# FonteTensaoVariavel.net
KiCad netlist of a schematic drawn in EAGLE
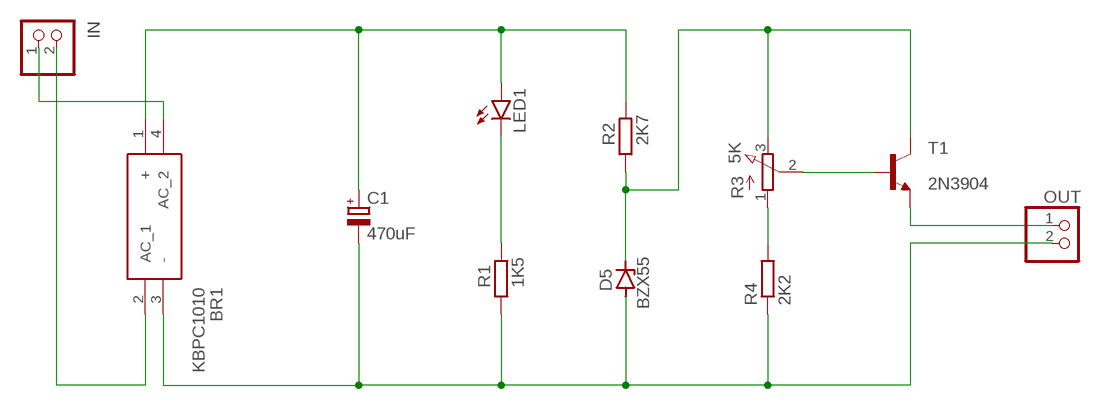
[diagram p0: schematic, sheet 1]

(export (version "E")
  (design (tool "Eeschema 10.0.6"))
  (components
    (comp (ref "BR1")
      (value "KBPC1010")
      (footprint "eagle-import:KBPC1010")
      (libsource (lib "eagle-import") (part "KBPC1010"))
    )
    (comp (ref "C1")
      (value "470uF")
      (footprint "eagle-import:E5-10,5")
      (libsource (lib "eagle-import") (part "CPOL-EUE5-10.5"))
    )
    (comp (ref "D5")
      (value "BZX55")
      (footprint "eagle-import:DO35Z10")
      (libsource (lib "eagle-import") (part "BZX55"))
    )
    (comp (ref "IN")
      (value "PINHD-1X2")
      (footprint "eagle-import:1X02")
      (libsource (lib "eagle-import") (part "PINHD-1X2"))
    )
    (comp (ref "LED1")
      (value "LED5MM")
      (footprint "eagle-import:LED5MM")
      (libsource (lib "eagle-import") (part "LED5MM"))
    )
    (comp (ref "OUT")
      (value "PINHD-1X2")
      (footprint "eagle-import:1X02")
      (libsource (lib "eagle-import") (part "PINHD-1X2"))
    )
    (comp (ref "R1")
      (value "1K5")
      (footprint "eagle-import:0207_10")
      (libsource (lib "eagle-import") (part "R-EU_0207/10"))
    )
    (comp (ref "R2")
      (value "2K7")
      (footprint "eagle-import:0207_10")
      (libsource (lib "eagle-import") (part "R-EU_0207/10"))
    )
    (comp (ref "R3")
      (value "5K")
      (footprint "eagle-import:3RP_1610N")
      (libsource (lib "eagle-import") (part "3RP/1610N"))
    )
    (comp (ref "R4")
      (value "2K2")
      (footprint "eagle-import:0207_10")
      (libsource (lib "eagle-import") (part "R-EU_0207/10"))
    )
    (comp (ref "T1")
      (value "2N3904")
      (footprint "eagle-import:TO92")
      (libsource (lib "eagle-import") (part "2N3904"))
    )
  )
  (nets
    (net (code "1") (name "Net-(BR1-+)") (class "Default")
      (node (ref "BR1") (pin "1") (pinfunction "+_1") (pintype "bidirectional"))
      (node (ref "C1") (pin "+") (pinfunction "+_+") (pintype "passive"))
      (node (ref "LED1") (pin "A") (pinfunction "A_A") (pintype "passive"))
      (node (ref "R2") (pin "2") (pinfunction "2_2") (pintype "passive"))
    )
    (net (code "2") (name "Net-(BR1--)") (class "Default")
      (node (ref "BR1") (pin "3") (pinfunction "-_3") (pintype "bidirectional"))
      (node (ref "C1") (pin "-") (pinfunction "-_-") (pintype "passive"))
      (node (ref "D5") (pin "A") (pinfunction "A_A") (pintype "passive"))
      (node (ref "OUT") (pin "2") (pinfunction "2_2") (pintype "passive"))
      (node (ref "R1") (pin "1") (pinfunction "1_1") (pintype "passive"))
      (node (ref "R4") (pin "1") (pinfunction "1_1") (pintype "passive"))
    )
    (net (code "3") (name "Net-(BR1-AC_1)") (class "Default")
      (node (ref "BR1") (pin "2") (pinfunction "AC_1_2") (pintype "bidirectional"))
      (node (ref "IN") (pin "2") (pinfunction "2_2") (pintype "passive"))
    )
    (net (code "4") (name "Net-(BR1-AC_2)") (class "Default")
      (node (ref "BR1") (pin "4") (pinfunction "AC_2_4") (pintype "bidirectional"))
      (node (ref "IN") (pin "1") (pinfunction "1_1") (pintype "passive"))
    )
    (net (code "5") (name "Net-(LED1-C)") (class "Default")
      (node (ref "LED1") (pin "K") (pinfunction "C_K") (pintype "passive"))
      (node (ref "R1") (pin "2") (pinfunction "2_2") (pintype "passive"))
    )
    (net (code "6") (name "Net-(R3-A)") (class "Default")
      (node (ref "R3") (pin "1") (pinfunction "A_1") (pintype "passive"))
      (node (ref "R4") (pin "2") (pinfunction "2_2") (pintype "passive"))
    )
    (net (code "7") (name "Net-(R3-E)") (class "Default")
      (node (ref "D5") (pin "C") (pinfunction "C_C") (pintype "passive"))
      (node (ref "R2") (pin "1") (pinfunction "1_1") (pintype "passive"))
      (node (ref "R3") (pin "3") (pinfunction "E_3") (pintype "passive"))
      (node (ref "T1") (pin "1") (pinfunction "C_1") (pintype "passive"))
    )
    (net (code "8") (name "Net-(R3-S)") (class "Default")
      (node (ref "R3") (pin "2") (pinfunction "S_2") (pintype "passive"))
      (node (ref "T1") (pin "2") (pinfunction "B_2") (pintype "passive"))
    )
    (net (code "9") (name "Net-(T1-E)") (class "Default")
      (node (ref "OUT") (pin "1") (pinfunction "1_1") (pintype "passive"))
      (node (ref "T1") (pin "3") (pinfunction "E_3") (pintype "passive"))
    )
  )
)
